# twpc.net
KiCad netlist of a schematic drawn in EAGLE
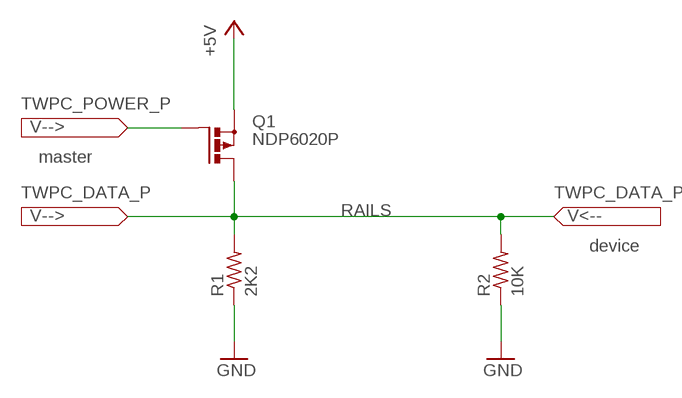
[diagram p0: schematic, sheet 1]

(export (version "E")
  (design (tool "Eeschema 10.0.6"))
  (components
    (comp (ref "Q1")
      (value "NDP6020P")
      (footprint "eagle-import:TO220BH")
      (libsource (lib "eagle-import") (part "PMOSFET_PTO220BH"))
    )
    (comp (ref "R1")
      (value "2K2")
      (footprint "eagle-import:0204_5")
      (libsource (lib "eagle-import") (part "R-US_0204/5"))
    )
    (comp (ref "R2")
      (value "10K")
      (footprint "eagle-import:0204V")
      (libsource (lib "eagle-import") (part "R-US_0204/2V"))
    )
  )
  (nets
    (net (code "1") (name "+5V") (class "Default")
      (node (ref "Q1") (pin "S") (pinfunction "S_S") (pintype "passive"))
    )
    (net (code "2") (name "GND") (class "Default")
      (node (ref "R1") (pin "1") (pinfunction "1_1") (pintype "passive"))
      (node (ref "R2") (pin "1") (pinfunction "1_1") (pintype "passive"))
    )
    (net (code "3") (name "Net-(Q1-PadD)") (class "Default")
      (node (ref "Q1") (pin "D") (pinfunction "D_D") (pintype "passive"))
      (node (ref "R1") (pin "2") (pinfunction "2_2") (pintype "passive"))
      (node (ref "R2") (pin "2") (pinfunction "2_2") (pintype "passive"))
    )
    (net (code "4") (name "unconnected-(Q1-PadG)") (class "Default")
      (node (ref "Q1") (pin "G") (pinfunction "G_G") (pintype "passive"))
    )
  )
)
